# PG05_DSP_Circuit.net
KiCad netlist of a schematic drawn in Altium Designer
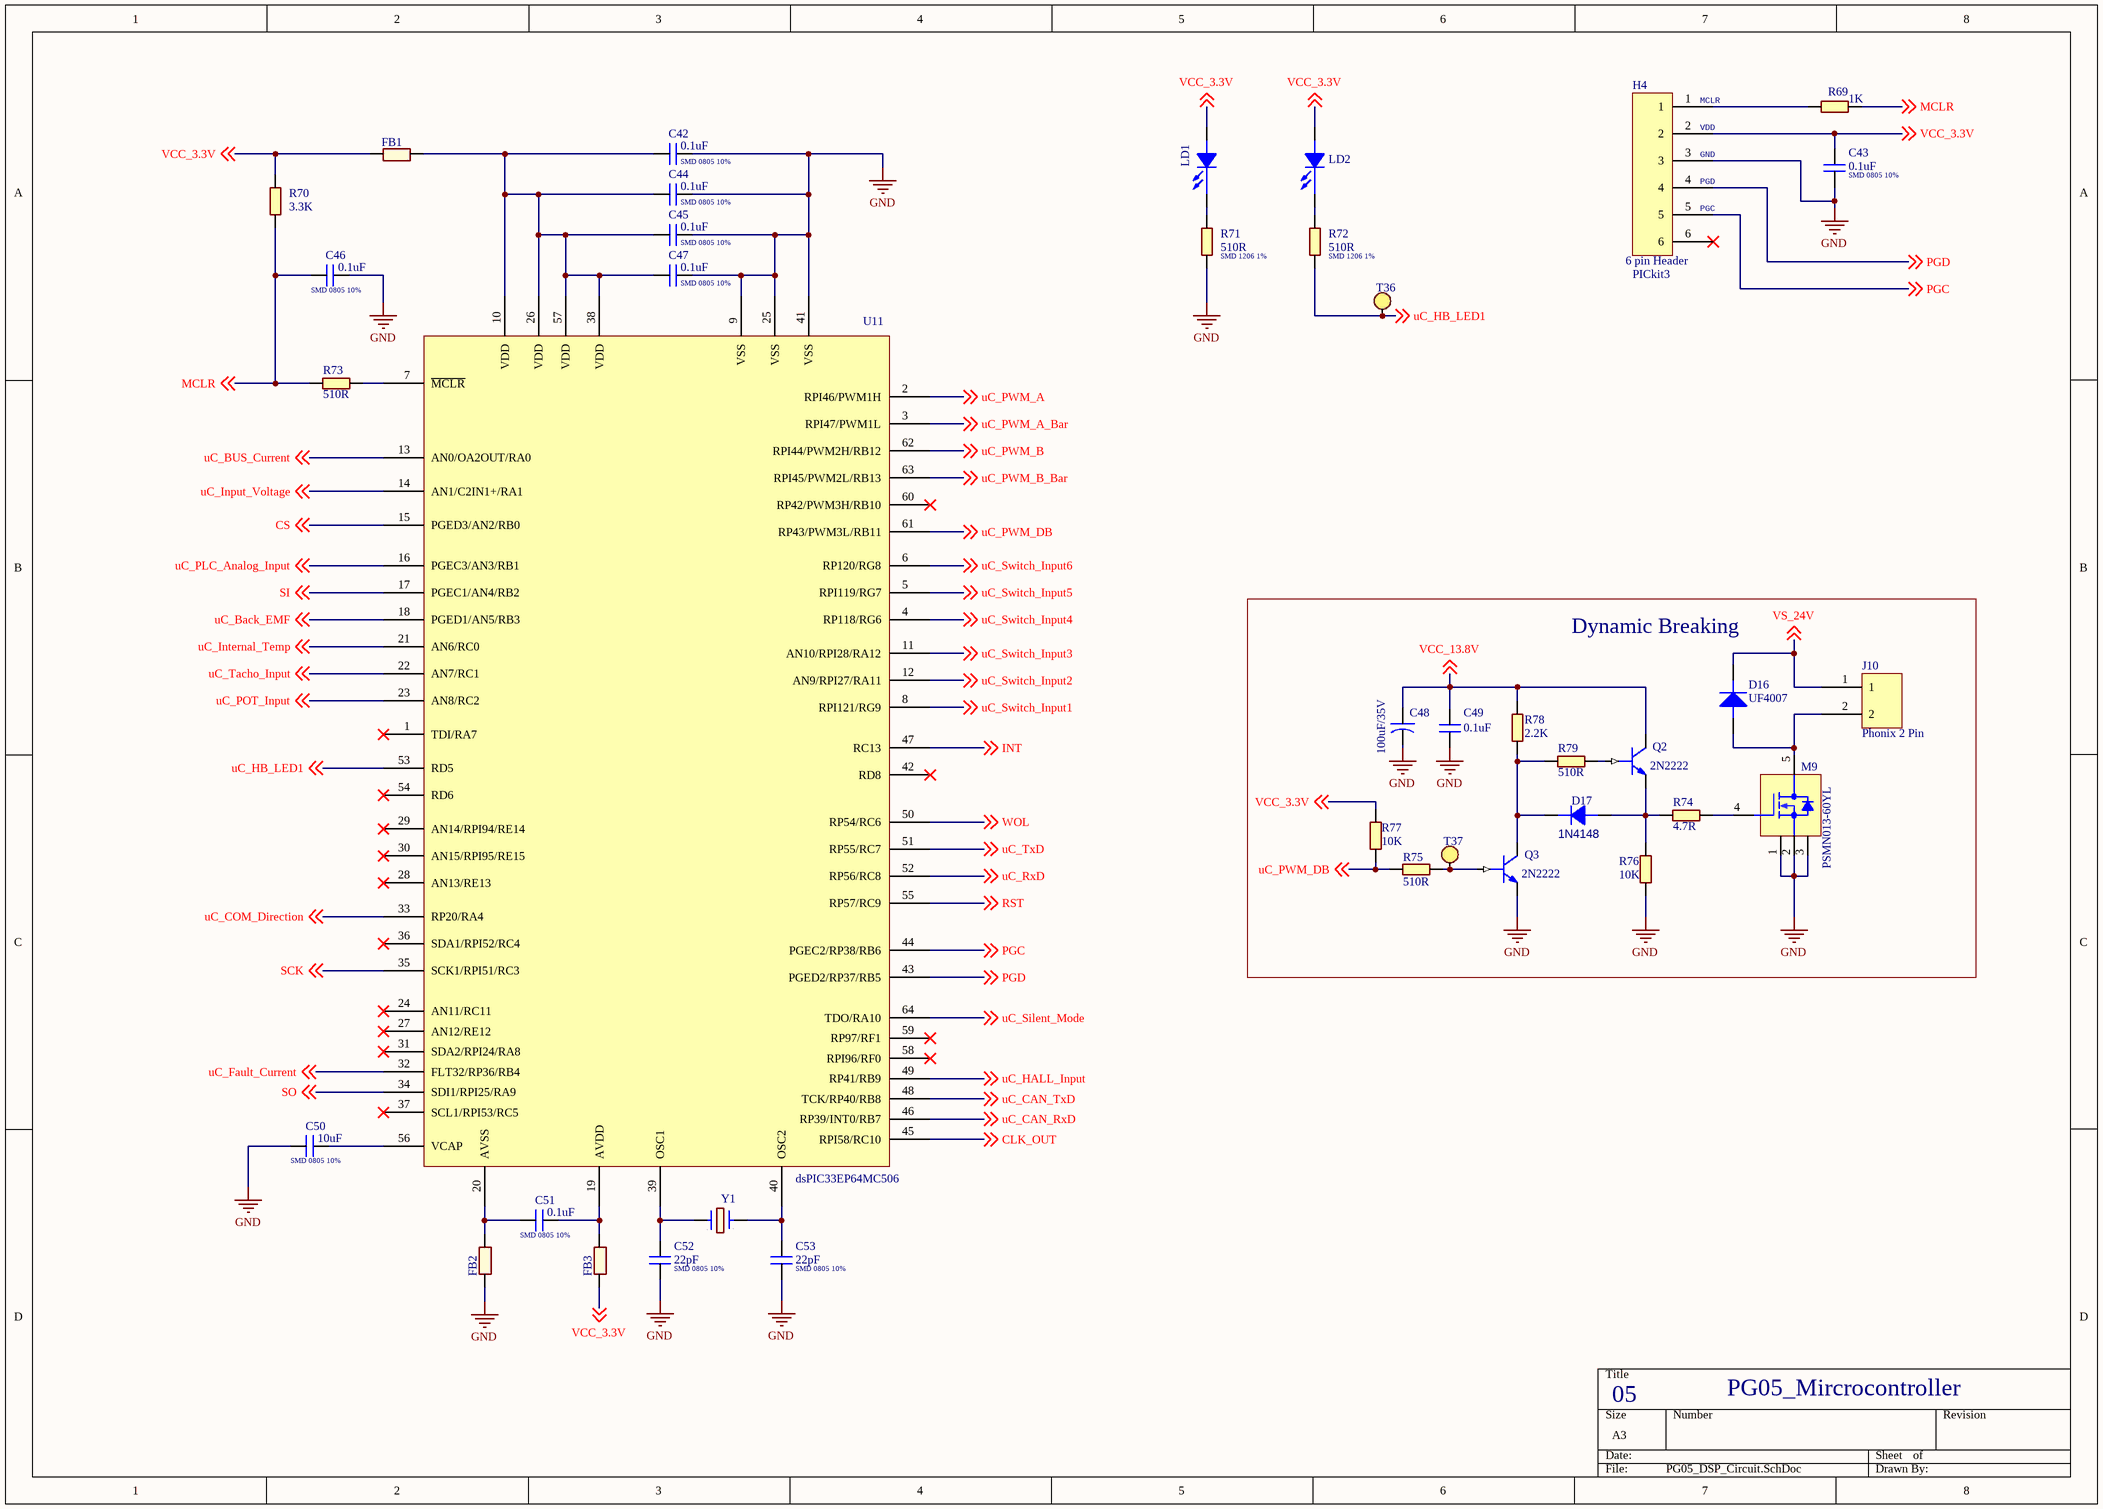
[diagram p0: PG05_DSP_Circuit.SchDoc]

(export (version "E")
  (design (tool "Eeschema 10.0.6"))
  (components
    (comp (ref "C42")
      (value "SMD 0805 10%")
      (footprint "SMD0805")
      (fields (field (name "MANUFACTURER") "Vishay") (field (name "ALTIUM_VALUE") "0.1uF"))
      (libsource (lib "Schlib1") (part "CAP_SMD"))
    )
    (comp (ref "C43")
      (value "SMD 0805 10%")
      (footprint "SMD0805")
      (fields (field (name "MANUFACTURER") "Vishay") (field (name "ALTIUM_VALUE") "0.1uF"))
      (libsource (lib "Schlib1") (part "CAP_SMD"))
    )
    (comp (ref "C44")
      (value "SMD 0805 10%")
      (footprint "SMD0805")
      (fields (field (name "MANUFACTURER") "Vishay") (field (name "ALTIUM_VALUE") "0.1uF"))
      (libsource (lib "Schlib1") (part "CAP_SMD"))
    )
    (comp (ref "C45")
      (value "SMD 0805 10%")
      (footprint "SMD0805")
      (fields (field (name "MANUFACTURER") "Vishay") (field (name "ALTIUM_VALUE") "0.1uF"))
      (libsource (lib "Schlib1") (part "CAP_SMD"))
    )
    (comp (ref "C46")
      (value "SMD 0805 10%")
      (footprint "SMD0805")
      (fields (field (name "MANUFACTURER") "Vishay") (field (name "ALTIUM_VALUE") "0.1uF"))
      (libsource (lib "Schlib1") (part "CAP_SMD"))
    )
    (comp (ref "C47")
      (value "SMD 0805 10%")
      (footprint "SMD0805")
      (fields (field (name "MANUFACTURER") "Vishay") (field (name "ALTIUM_VALUE") "0.1uF"))
      (libsource (lib "Schlib1") (part "CAP_SMD"))
    )
    (comp (ref "C48")
      (value "100uF/35V")
      (footprint "CAP_8mm")
      (fields (field (name "MANUFACTURER") "Nichicon") (field (name "Comment") "Cap 5mm radial"))
      (libsource (lib "Schlib1") (part "CAP_Electolytic_5mm"))
    )
    (comp (ref "C49")
      (value "0.1uF")
      (footprint "SMD0805")
      (fields (field (name "MANUFACTURER") "Vishay") (field (name "Comment") "SMD 0805 10%"))
      (libsource (lib "Schlib1") (part "CAP_SMD"))
    )
    (comp (ref "C50")
      (value "SMD 0805 10%")
      (footprint "SMD0805")
      (fields (field (name "MANUFACTURER") "Vishay") (field (name "ALTIUM_VALUE") "10uF"))
      (libsource (lib "Schlib1") (part "CAP_SMD"))
    )
    (comp (ref "C51")
      (value "SMD 0805 10%")
      (footprint "SMD0805")
      (fields (field (name "MANUFACTURER") "Vishay") (field (name "ALTIUM_VALUE") "0.1uF"))
      (libsource (lib "Schlib1") (part "CAP_SMD"))
    )
    (comp (ref "C52")
      (value "SMD 0805 10%")
      (footprint "SMD0805")
      (fields (field (name "MANUFACTURER") "Vishay") (field (name "ALTIUM_VALUE") "22pF"))
      (libsource (lib "Schlib1") (part "CAP_SMD"))
    )
    (comp (ref "C53")
      (value "SMD 0805 10%")
      (footprint "SMD0805")
      (fields (field (name "MANUFACTURER") "Vishay") (field (name "ALTIUM_VALUE") "22pF"))
      (libsource (lib "Schlib1") (part "CAP_SMD"))
    )
    (comp (ref "D16")
      (value "UF4007")
      (footprint "DO-214(SMA)")
      (fields (field (name "MANUFACTURER") "Diodes Corp") (field (name "Comment") "Diode SMA"))
      (libsource (lib "Schlib1") (part "Diode_SMA"))
    )
    (comp (ref "D17")
      (value "1N4148")
      (fields
        (field (name "PART NO.") "SM4007")
        (field (name "TOLERANCE") "10%")
        (field (name "MANUFACTURER") "Vishay")
      )
      (libsource (lib "*") (part "1N4148"))
    )
    (comp (ref "FB1")
      (value "Ferrite Bead")
      (fields (field (name "MANUFACTURER") "Vishay Semiconductors"))
      (libsource (lib "*") (part "R_3"))
    )
    (comp (ref "FB2")
      (value "Ferrite Bead")
      (fields (field (name "MANUFACTURER") "Vishay Semiconductors"))
      (libsource (lib "") (part "R_3_1"))
    )
    (comp (ref "FB3")
      (value "Ferrite Bead")
      (fields (field (name "MANUFACTURER") "Vishay Semiconductors"))
      (libsource (lib "") (part "R_3_1"))
    )
    (comp (ref "H4")
      (value "PICkit3")
      (footprint "Header1x6")
      (fields (field (name "ALTIUM_VALUE") "6 pin Header"))
      (libsource (lib "Schlib1") (part "Header_6_Pin"))
    )
    (comp (ref "J10")
      (value "Phonix 2 Pin")
      (footprint "PHONIX2")
      (libsource (lib "Schlib1") (part "Phonix_2_Pin"))
    )
    (comp (ref "LD1")
      (value "LED")
      (fields (field (name "MANUFACTURER") "Rajeev"))
      (libsource (lib "*") (part "LED"))
    )
    (comp (ref "LD2")
      (value "LED")
      (fields (field (name "MANUFACTURER") "Rajeev"))
      (libsource (lib "*") (part "LED"))
    )
    (comp (ref "M9")
      (value "PSMN013-60YL")
      (footprint "SO8-L")
      (fields (field (name "MANUFACTURER") "NxP") (field (name "Comment") "N MOSFET"))
      (libsource (lib "Schlib1") (part "MOS_PSMN013-60YL"))
    )
    (comp (ref "Q2")
      (value "2N2222")
      (fields (field (name "MANUFACTURER") "OnSemi") (field (name "Comment") "SMD NPN BJT"))
      (libsource (lib "*") (part "2N3904_1"))
    )
    (comp (ref "Q3")
      (value "2N2222")
      (fields (field (name "MANUFACTURER") "OnSemi") (field (name "Comment") "SMD NPN BJT"))
      (libsource (lib "*") (part "2N3904_1"))
    )
    (comp (ref "R69")
      (value "1K")
      (footprint "SMD1206")
      (description "SMD1206  1% Resistor")
      (fields (field (name "MANUFACTURER") "Vishay") (field (name "Comment") "SMD 1206 1%"))
      (libsource (lib "") (part "RES_SMD_1"))
    )
    (comp (ref "R70")
      (value "3.3K")
      (footprint "SMD1206")
      (description "SMD1206  1% Resistor")
      (fields (field (name "MANUFACTURER") "Vishay") (field (name "Comment") "SMD 1206 1%"))
      (libsource (lib "Schlib1") (part "RES_SMD"))
    )
    (comp (ref "R71")
      (value "SMD 1206 1%")
      (footprint "SMD1206")
      (description "SMD1206  1% Resistor")
      (fields (field (name "MANUFACTURER") "Vishay") (field (name "ALTIUM_VALUE") "510R"))
      (libsource (lib "") (part "RES_SMD_2"))
    )
    (comp (ref "R72")
      (value "SMD 1206 1%")
      (footprint "SMD1206")
      (description "SMD1206  1% Resistor")
      (fields (field (name "MANUFACTURER") "Vishay") (field (name "ALTIUM_VALUE") "510R"))
      (libsource (lib "") (part "RES_SMD_2"))
    )
    (comp (ref "R73")
      (value "510R")
      (footprint "SMD1206")
      (description "SMD1206  1% Resistor")
      (fields (field (name "MANUFACTURER") "Vishay") (field (name "Comment") "SMD 1206 1%"))
      (libsource (lib "") (part "RES_SMD_1"))
    )
    (comp (ref "R74")
      (value "4.7R")
      (footprint "SMD1206")
      (description "SMD1206  1% Resistor")
      (fields (field (name "MANUFACTURER") "Vishay") (field (name "Comment") "SMD 1206 1%"))
      (libsource (lib "") (part "RES_SMD_1"))
    )
    (comp (ref "R75")
      (value "510R")
      (footprint "SMD1206")
      (description "SMD1206  1% Resistor")
      (fields (field (name "MANUFACTURER") "Vishay") (field (name "Comment") "SMD 1206 1%"))
      (libsource (lib "") (part "RES_SMD_3"))
    )
    (comp (ref "R76")
      (value "10K")
      (footprint "SMD1206")
      (description "SMD1206  1% Resistor")
      (fields (field (name "MANUFACTURER") "Vishay") (field (name "Comment") "SMD 1206 1%"))
      (libsource (lib "") (part "RES_SMD_2"))
    )
    (comp (ref "R77")
      (value "10K")
      (footprint "SMD1206")
      (description "SMD1206  1% Resistor")
      (fields (field (name "MANUFACTURER") "Vishay") (field (name "Comment") "SMD 1206 1%"))
      (libsource (lib "Schlib1") (part "RES_SMD"))
    )
    (comp (ref "R78")
      (value "2.2K")
      (footprint "SMD1206")
      (description "SMD1206  1% Resistor")
      (fields (field (name "MANUFACTURER") "Vishay") (field (name "Comment") "SMD 1206 1%"))
      (libsource (lib "") (part "RES_SMD_2"))
    )
    (comp (ref "R79")
      (value "510R")
      (footprint "SMD1206")
      (description "SMD1206  1% Resistor")
      (fields (field (name "MANUFACTURER") "Vishay") (field (name "Comment") "SMD 1206 1%"))
      (libsource (lib "") (part "RES_SMD_3"))
    )
    (comp (ref "T36")
      (value "Through hole TestPoint")
      (footprint "TP")
      (libsource (lib "Schlib1") (part "TestPoint_TH"))
    )
    (comp (ref "T37")
      (value "Through hole TestPoint")
      (footprint "TP")
      (libsource (lib "Schlib1") (part "TestPoint_TH"))
    )
    (comp (ref "U11")
      (value "dsPIC33EP64MC506")
      (footprint "Quad64")
      (fields (field (name "MANUFACTURER") "Microchip") (field (name "Comment") "DSP"))
      (libsource (lib "Schlib1") (part "dsPIC33EP64MC506"))
    )
    (comp (ref "Y1") (value "7.3728MHz") (footprint "XTAL") (libsource (lib "Schlib1") (part "Crystal")))
  )
  (nets
    (net (code "1") (name "CLK_OUT") (class "Default")
      (node (ref "U11") (pin "45") (pinfunction "RPI58/RC10_45") (pintype "passive"))
    )
    (net (code "2") (name "CS") (class "Default")
      (node (ref "U11") (pin "15") (pinfunction "PGED3/AN2/RB0_15") (pintype "passive"))
    )
    (net (code "3") (name "GND") (class "Default")
      (node (ref "C42") (pin "2") (pinfunction "2_2") (pintype "passive"))
      (node (ref "C43") (pin "1") (pinfunction "1_1") (pintype "passive"))
      (node (ref "C44") (pin "2") (pinfunction "2_2") (pintype "passive"))
      (node (ref "C45") (pin "2") (pinfunction "2_2") (pintype "passive"))
      (node (ref "C46") (pin "2") (pinfunction "2_2") (pintype "passive"))
      (node (ref "C47") (pin "2") (pinfunction "2_2") (pintype "passive"))
      (node (ref "C48") (pin "2") (pinfunction "2_2") (pintype "passive"))
      (node (ref "C49") (pin "2") (pinfunction "2_2") (pintype "passive"))
      (node (ref "C50") (pin "1") (pinfunction "1_1") (pintype "passive"))
      (node (ref "C52") (pin "1") (pinfunction "1_1") (pintype "passive"))
      (node (ref "C53") (pin "1") (pinfunction "1_1") (pintype "passive"))
      (node (ref "FB2") (pin "2") (pinfunction "2_2") (pintype "passive"))
      (node (ref "H4") (pin "3") (pinfunction "3_3") (pintype "passive"))
      (node (ref "M9") (pin "1") (pinfunction "1_1") (pintype "passive"))
      (node (ref "M9") (pin "2") (pinfunction "2_2") (pintype "passive"))
      (node (ref "M9") (pin "3") (pinfunction "3_3") (pintype "passive"))
      (node (ref "Q3") (pin "2") (pinfunction "EMITTER_2") (pintype "passive"))
      (node (ref "R71") (pin "2") (pinfunction "2_2") (pintype "passive"))
      (node (ref "R76") (pin "2") (pinfunction "2_2") (pintype "passive"))
      (node (ref "U11") (pin "25") (pinfunction "VSS_25") (pintype "passive"))
      (node (ref "U11") (pin "41") (pinfunction "VSS_41") (pintype "passive"))
      (node (ref "U11") (pin "9") (pinfunction "VSS_9") (pintype "passive"))
    )
    (net (code "4") (name "INT") (class "Default")
      (node (ref "U11") (pin "47") (pinfunction "RC13_47") (pintype "passive"))
    )
    (net (code "5") (name "MCLR") (class "Default")
      (node (ref "C46") (pin "1") (pinfunction "1_1") (pintype "passive"))
      (node (ref "R69") (pin "1") (pinfunction "1_1") (pintype "passive"))
      (node (ref "R70") (pin "1") (pinfunction "1_1") (pintype "passive"))
      (node (ref "R73") (pin "2") (pinfunction "2_2") (pintype "passive"))
    )
    (net (code "6") (name "Net-(C42-Pad1)") (class "Default")
      (node (ref "C42") (pin "1") (pinfunction "1_1") (pintype "passive"))
      (node (ref "C44") (pin "1") (pinfunction "1_1") (pintype "passive"))
      (node (ref "C45") (pin "1") (pinfunction "1_1") (pintype "passive"))
      (node (ref "C47") (pin "1") (pinfunction "1_1") (pintype "passive"))
      (node (ref "FB1") (pin "1") (pinfunction "1_1") (pintype "passive"))
      (node (ref "U11") (pin "10") (pinfunction "VDD_10") (pintype "passive"))
      (node (ref "U11") (pin "26") (pinfunction "VDD_26") (pintype "passive"))
      (node (ref "U11") (pin "38") (pinfunction "VDD_38") (pintype "passive"))
      (node (ref "U11") (pin "57") (pinfunction "VDD_57") (pintype "passive"))
    )
    (net (code "7") (name "Net-(D16-Pad1)") (class "Default")
      (node (ref "D16") (pin "1") (pintype "passive"))
      (node (ref "J10") (pin "2") (pinfunction "2_2") (pintype "passive"))
      (node (ref "M9") (pin "5") (pinfunction "5_5") (pintype "passive"))
    )
    (net (code "8") (name "Net-(D17-ANODE)") (class "Default")
      (node (ref "D17") (pin "1") (pinfunction "ANODE_1") (pintype "passive"))
      (node (ref "Q2") (pin "2") (pinfunction "EMITTER_2") (pintype "passive"))
      (node (ref "R74") (pin "2") (pinfunction "2_2") (pintype "passive"))
      (node (ref "R76") (pin "1") (pinfunction "1_1") (pintype "passive"))
    )
    (net (code "9") (name "Net-(D17-CATHODE)") (class "Default")
      (node (ref "D17") (pin "2") (pinfunction "CATHODE_2") (pintype "passive"))
      (node (ref "Q3") (pin "3") (pinfunction "COLLECTOR_3") (pintype "passive"))
      (node (ref "R78") (pin "2") (pinfunction "2_2") (pintype "passive"))
      (node (ref "R79") (pin "1") (pinfunction "1_1") (pintype "passive"))
    )
    (net (code "10") (name "Net-(H4-Pad1)") (class "Default")
      (node (ref "H4") (pin "1") (pinfunction "1_1") (pintype "passive"))
      (node (ref "R69") (pin "2") (pinfunction "2_2") (pintype "passive"))
    )
    (net (code "11") (name "Net-(LD1-CATHODE)") (class "Default")
      (node (ref "LD1") (pin "2") (pinfunction "CATHODE_2") (pintype "passive"))
      (node (ref "R71") (pin "1") (pinfunction "1_1") (pintype "passive"))
    )
    (net (code "12") (name "Net-(LD2-CATHODE)") (class "Default")
      (node (ref "LD2") (pin "2") (pinfunction "CATHODE_2") (pintype "passive"))
      (node (ref "R72") (pin "1") (pinfunction "1_1") (pintype "passive"))
    )
    (net (code "13") (name "Net-(M9-G)") (class "Default")
      (node (ref "M9") (pin "4") (pinfunction "G_4") (pintype "passive"))
      (node (ref "R74") (pin "1") (pinfunction "1_1") (pintype "passive"))
    )
    (net (code "14") (name "Net-(Q2-BASE)") (class "Default")
      (node (ref "Q2") (pin "1") (pinfunction "BASE_1") (pintype "input"))
      (node (ref "R79") (pin "2") (pinfunction "2_2") (pintype "passive"))
    )
    (net (code "15") (name "Net-(Q3-BASE)") (class "Default")
      (node (ref "Q3") (pin "1") (pinfunction "BASE_1") (pintype "input"))
      (node (ref "R75") (pin "2") (pinfunction "2_2") (pintype "passive"))
      (node (ref "T37") (pin "1") (pintype "passive"))
    )
    (net (code "16") (name "Net-(U11-AVDD)") (class "Default")
      (node (ref "C51") (pin "2") (pinfunction "2_2") (pintype "passive"))
      (node (ref "FB3") (pin "1") (pinfunction "1_1") (pintype "passive"))
      (node (ref "U11") (pin "19") (pinfunction "AVDD_19") (pintype "passive"))
    )
    (net (code "17") (name "Net-(U11-AVSS)") (class "Default")
      (node (ref "C51") (pin "1") (pinfunction "1_1") (pintype "passive"))
      (node (ref "FB2") (pin "1") (pinfunction "1_1") (pintype "passive"))
      (node (ref "U11") (pin "20") (pinfunction "AVSS_20") (pintype "passive"))
    )
    (net (code "18") (name "Net-(U11-OSC1)") (class "Default")
      (node (ref "C52") (pin "2") (pinfunction "2_2") (pintype "passive"))
      (node (ref "U11") (pin "39") (pinfunction "OSC1_39") (pintype "passive"))
      (node (ref "Y1") (pin "1") (pinfunction "1_1") (pintype "passive"))
    )
    (net (code "19") (name "Net-(U11-OSC2)") (class "Default")
      (node (ref "C53") (pin "2") (pinfunction "2_2") (pintype "passive"))
      (node (ref "U11") (pin "40") (pinfunction "OSC2_40") (pintype "passive"))
      (node (ref "Y1") (pin "2") (pinfunction "2_2") (pintype "passive"))
    )
    (net (code "20") (name "Net-(U11-VCAP)") (class "Default")
      (node (ref "C50") (pin "2") (pinfunction "2_2") (pintype "passive"))
      (node (ref "U11") (pin "56") (pinfunction "VCAP_56") (pintype "passive"))
    )
    (net (code "21") (name "Net-(U11-~{MCLR})") (class "Default")
      (node (ref "R73") (pin "1") (pinfunction "1_1") (pintype "passive"))
      (node (ref "U11") (pin "7") (pinfunction "~{MCLR}_7") (pintype "passive"))
    )
    (net (code "22") (name "PGC") (class "Default")
      (node (ref "H4") (pin "5") (pinfunction "5_5") (pintype "passive"))
      (node (ref "U11") (pin "44") (pinfunction "PGEC2/RP38/RB6_44") (pintype "passive"))
    )
    (net (code "23") (name "PGD") (class "Default")
      (node (ref "H4") (pin "4") (pinfunction "4_4") (pintype "passive"))
      (node (ref "U11") (pin "43") (pinfunction "PGED2/RP37/RB5_43") (pintype "passive"))
    )
    (net (code "24") (name "RST") (class "Default")
      (node (ref "U11") (pin "55") (pinfunction "RP57/RC9_55") (pintype "passive"))
    )
    (net (code "25") (name "SCK") (class "Default")
      (node (ref "U11") (pin "35") (pinfunction "SCK1/RPI51/RC3_35") (pintype "passive"))
    )
    (net (code "26") (name "SI") (class "Default")
      (node (ref "U11") (pin "17") (pinfunction "PGEC1/AN4/RB2_17") (pintype "passive"))
    )
    (net (code "27") (name "SO") (class "Default")
      (node (ref "U11") (pin "34") (pinfunction "SDI1/RPI25/RA9_34") (pintype "passive"))
    )
    (net (code "28") (name "VCC_3.3V") (class "Default")
      (node (ref "C43") (pin "2") (pinfunction "2_2") (pintype "passive"))
      (node (ref "FB1") (pin "2") (pinfunction "2_2") (pintype "passive"))
      (node (ref "FB3") (pin "2") (pinfunction "2_2") (pintype "passive"))
      (node (ref "H4") (pin "2") (pinfunction "2_2") (pintype "passive"))
      (node (ref "LD1") (pin "1") (pinfunction "ANODE_1") (pintype "passive"))
      (node (ref "LD2") (pin "1") (pinfunction "ANODE_1") (pintype "passive"))
      (node (ref "R70") (pin "2") (pinfunction "2_2") (pintype "passive"))
      (node (ref "R77") (pin "2") (pinfunction "2_2") (pintype "passive"))
    )
    (net (code "29") (name "VCC_13.8V") (class "Default")
      (node (ref "C48") (pin "1") (pinfunction "1_1") (pintype "passive"))
      (node (ref "C49") (pin "1") (pinfunction "1_1") (pintype "passive"))
      (node (ref "Q2") (pin "3") (pinfunction "COLLECTOR_3") (pintype "passive"))
      (node (ref "R78") (pin "1") (pinfunction "1_1") (pintype "passive"))
    )
    (net (code "30") (name "VS_24V") (class "Default")
      (node (ref "D16") (pin "2") (pintype "passive"))
      (node (ref "J10") (pin "1") (pinfunction "1_1") (pintype "passive"))
    )
    (net (code "31") (name "WOL") (class "Default")
      (node (ref "U11") (pin "50") (pinfunction "RP54/RC6_50") (pintype "passive"))
    )
    (net (code "32") (name "uC_BUS_Current") (class "Default")
      (node (ref "U11") (pin "13") (pinfunction "AN0/OA2OUT/RA0_13") (pintype "passive"))
    )
    (net (code "33") (name "uC_Back_EMF") (class "Default")
      (node (ref "U11") (pin "18") (pinfunction "PGED1/AN5/RB3_18") (pintype "passive"))
    )
    (net (code "34") (name "uC_CAN_RxD") (class "Default")
      (node (ref "U11") (pin "46") (pinfunction "RP39/INT0/RB7_46") (pintype "passive"))
    )
    (net (code "35") (name "uC_CAN_TxD") (class "Default")
      (node (ref "U11") (pin "48") (pinfunction "TCK/RP40/RB8_48") (pintype "passive"))
    )
    (net (code "36") (name "uC_COM_Direction") (class "Default")
      (node (ref "U11") (pin "33") (pinfunction "RP20/RA4_33") (pintype "passive"))
    )
    (net (code "37") (name "uC_Fault_Current") (class "Default")
      (node (ref "U11") (pin "32") (pinfunction "FLT32/RP36/RB4_32") (pintype "passive"))
    )
    (net (code "38") (name "uC_HALL_Input") (class "Default")
      (node (ref "U11") (pin "49") (pinfunction "RP41/RB9_49") (pintype "passive"))
    )
    (net (code "39") (name "uC_HB_LED1") (class "Default")
      (node (ref "R72") (pin "2") (pinfunction "2_2") (pintype "passive"))
      (node (ref "T36") (pin "1") (pintype "passive"))
      (node (ref "U11") (pin "53") (pinfunction "RD5_53") (pintype "passive"))
    )
    (net (code "40") (name "uC_Input_Voltage") (class "Default")
      (node (ref "U11") (pin "14") (pinfunction "AN1/C2IN1+/RA1_14") (pintype "passive"))
    )
    (net (code "41") (name "uC_Internal_Temp") (class "Default")
      (node (ref "U11") (pin "21") (pinfunction "AN6/RC0_21") (pintype "passive"))
    )
    (net (code "42") (name "uC_PLC_Analog_Input") (class "Default")
      (node (ref "U11") (pin "16") (pinfunction "PGEC3/AN3/RB1_16") (pintype "passive"))
    )
    (net (code "43") (name "uC_POT_Input") (class "Default")
      (node (ref "U11") (pin "23") (pinfunction "AN8/RC2_23") (pintype "passive"))
    )
    (net (code "44") (name "uC_PWM_A") (class "Default")
      (node (ref "U11") (pin "2") (pinfunction "RPI46/PWM1H_2") (pintype "passive"))
    )
    (net (code "45") (name "uC_PWM_A_Bar") (class "Default")
      (node (ref "U11") (pin "3") (pinfunction "RPI47/PWM1L_3") (pintype "passive"))
    )
    (net (code "46") (name "uC_PWM_B") (class "Default")
      (node (ref "U11") (pin "62") (pinfunction "RPI44/PWM2H/RB12_62") (pintype "passive"))
    )
    (net (code "47") (name "uC_PWM_B_Bar") (class "Default")
      (node (ref "U11") (pin "63") (pinfunction "RPI45/PWM2L/RB13_63") (pintype "passive"))
    )
    (net (code "48") (name "uC_PWM_DB") (class "Default")
      (node (ref "R75") (pin "1") (pinfunction "1_1") (pintype "passive"))
      (node (ref "R77") (pin "1") (pinfunction "1_1") (pintype "passive"))
      (node (ref "U11") (pin "61") (pinfunction "RP43/PWM3L/RB11_61") (pintype "passive"))
    )
    (net (code "49") (name "uC_RxD") (class "Default")
      (node (ref "U11") (pin "52") (pinfunction "RP56/RC8_52") (pintype "passive"))
    )
    (net (code "50") (name "uC_Silent_Mode") (class "Default")
      (node (ref "U11") (pin "64") (pinfunction "TDO/RA10_64") (pintype "passive"))
    )
    (net (code "51") (name "uC_Switch_Input1") (class "Default")
      (node (ref "U11") (pin "8") (pinfunction "RPI121/RG9_8") (pintype "passive"))
    )
    (net (code "52") (name "uC_Switch_Input2") (class "Default")
      (node (ref "U11") (pin "12") (pinfunction "AN9/RPI27/RA11_12") (pintype "passive"))
    )
    (net (code "53") (name "uC_Switch_Input3") (class "Default")
      (node (ref "U11") (pin "11") (pinfunction "AN10/RPI28/RA12_11") (pintype "passive"))
    )
    (net (code "54") (name "uC_Switch_Input4") (class "Default")
      (node (ref "U11") (pin "4") (pinfunction "RP118/RG6_4") (pintype "passive"))
    )
    (net (code "55") (name "uC_Switch_Input5") (class "Default")
      (node (ref "U11") (pin "5") (pinfunction "RPI119/RG7_5") (pintype "passive"))
    )
    (net (code "56") (name "uC_Switch_Input6") (class "Default")
      (node (ref "U11") (pin "6") (pinfunction "RP120/RG8_6") (pintype "passive"))
    )
    (net (code "57") (name "uC_Tacho_Input") (class "Default")
      (node (ref "U11") (pin "22") (pinfunction "AN7/RC1_22") (pintype "passive"))
    )
    (net (code "58") (name "uC_TxD") (class "Default")
      (node (ref "U11") (pin "51") (pinfunction "RP55/RC7_51") (pintype "passive"))
    )
    (net (code "59") (name "unconnected-(H4-Pad6)") (class "Default")
      (node (ref "H4") (pin "6") (pinfunction "6_6") (pintype "passive+no_connect"))
    )
    (net (code "60") (name "unconnected-(U11-AN11{slash}RC11-Pad24)") (class "Default")
      (node (ref "U11") (pin "24") (pinfunction "AN11/RC11_24") (pintype "passive+no_connect"))
    )
    (net (code "61") (name "unconnected-(U11-AN12{slash}RE12-Pad27)") (class "Default")
      (node (ref "U11") (pin "27") (pinfunction "AN12/RE12_27") (pintype "passive+no_connect"))
    )
    (net (code "62") (name "unconnected-(U11-AN13{slash}RE13-Pad28)") (class "Default")
      (node (ref "U11") (pin "28") (pinfunction "AN13/RE13_28") (pintype "passive+no_connect"))
    )
    (net (code "63") (name "unconnected-(U11-AN14{slash}RPI94{slash}RE14-Pad29)") (class "Default")
      (node (ref "U11") (pin "29") (pinfunction "AN14/RPI94/RE14_29") (pintype "passive+no_connect"))
    )
    (net (code "64") (name "unconnected-(U11-AN15{slash}RPI95{slash}RE15-Pad30)") (class "Default")
      (node (ref "U11") (pin "30") (pinfunction "AN15/RPI95/RE15_30") (pintype "passive+no_connect"))
    )
    (net (code "65") (name "unconnected-(U11-RD6-Pad54)") (class "Default")
      (node (ref "U11") (pin "54") (pinfunction "RD6_54") (pintype "passive+no_connect"))
    )
    (net (code "66") (name "unconnected-(U11-RD8-Pad42)") (class "Default")
      (node (ref "U11") (pin "42") (pinfunction "RD8_42") (pintype "passive+no_connect"))
    )
    (net (code "67") (name "unconnected-(U11-RP42{slash}PWM3H{slash}RB10-Pad60)") (class "Default")
      (node (ref "U11") (pin "60") (pinfunction "RP42/PWM3H/RB10_60") (pintype "passive+no_connect"))
    )
    (net (code "68") (name "unconnected-(U11-RP97{slash}RF1-Pad59)") (class "Default")
      (node (ref "U11") (pin "59") (pinfunction "RP97/RF1_59") (pintype "passive+no_connect"))
    )
    (net (code "69") (name "unconnected-(U11-RPI96{slash}RF0-Pad58)") (class "Default")
      (node (ref "U11") (pin "58") (pinfunction "RPI96/RF0_58") (pintype "passive+no_connect"))
    )
    (net (code "70") (name "unconnected-(U11-SCL1{slash}RPI53{slash}RC5-Pad37)") (class "Default")
      (node (ref "U11") (pin "37") (pinfunction "SCL1/RPI53/RC5_37") (pintype "passive+no_connect"))
    )
    (net (code "71") (name "unconnected-(U11-SDA1{slash}RPI52{slash}RC4-Pad36)") (class "Default")
      (node (ref "U11") (pin "36") (pinfunction "SDA1/RPI52/RC4_36") (pintype "passive+no_connect"))
    )
    (net (code "72") (name "unconnected-(U11-SDA2{slash}RPI24{slash}RA8-Pad31)") (class "Default")
      (node (ref "U11") (pin "31") (pinfunction "SDA2/RPI24/RA8_31") (pintype "passive+no_connect"))
    )
    (net (code "73") (name "unconnected-(U11-TDI{slash}RA7-Pad1)") (class "Default")
      (node (ref "U11") (pin "1") (pinfunction "TDI/RA7_1") (pintype "passive+no_connect"))
    )
  )
)
